# 780-00041_rev1_Front_Panel_Mirror_Cell_C.net
KiCad netlist of a schematic drawn in Altium Designer
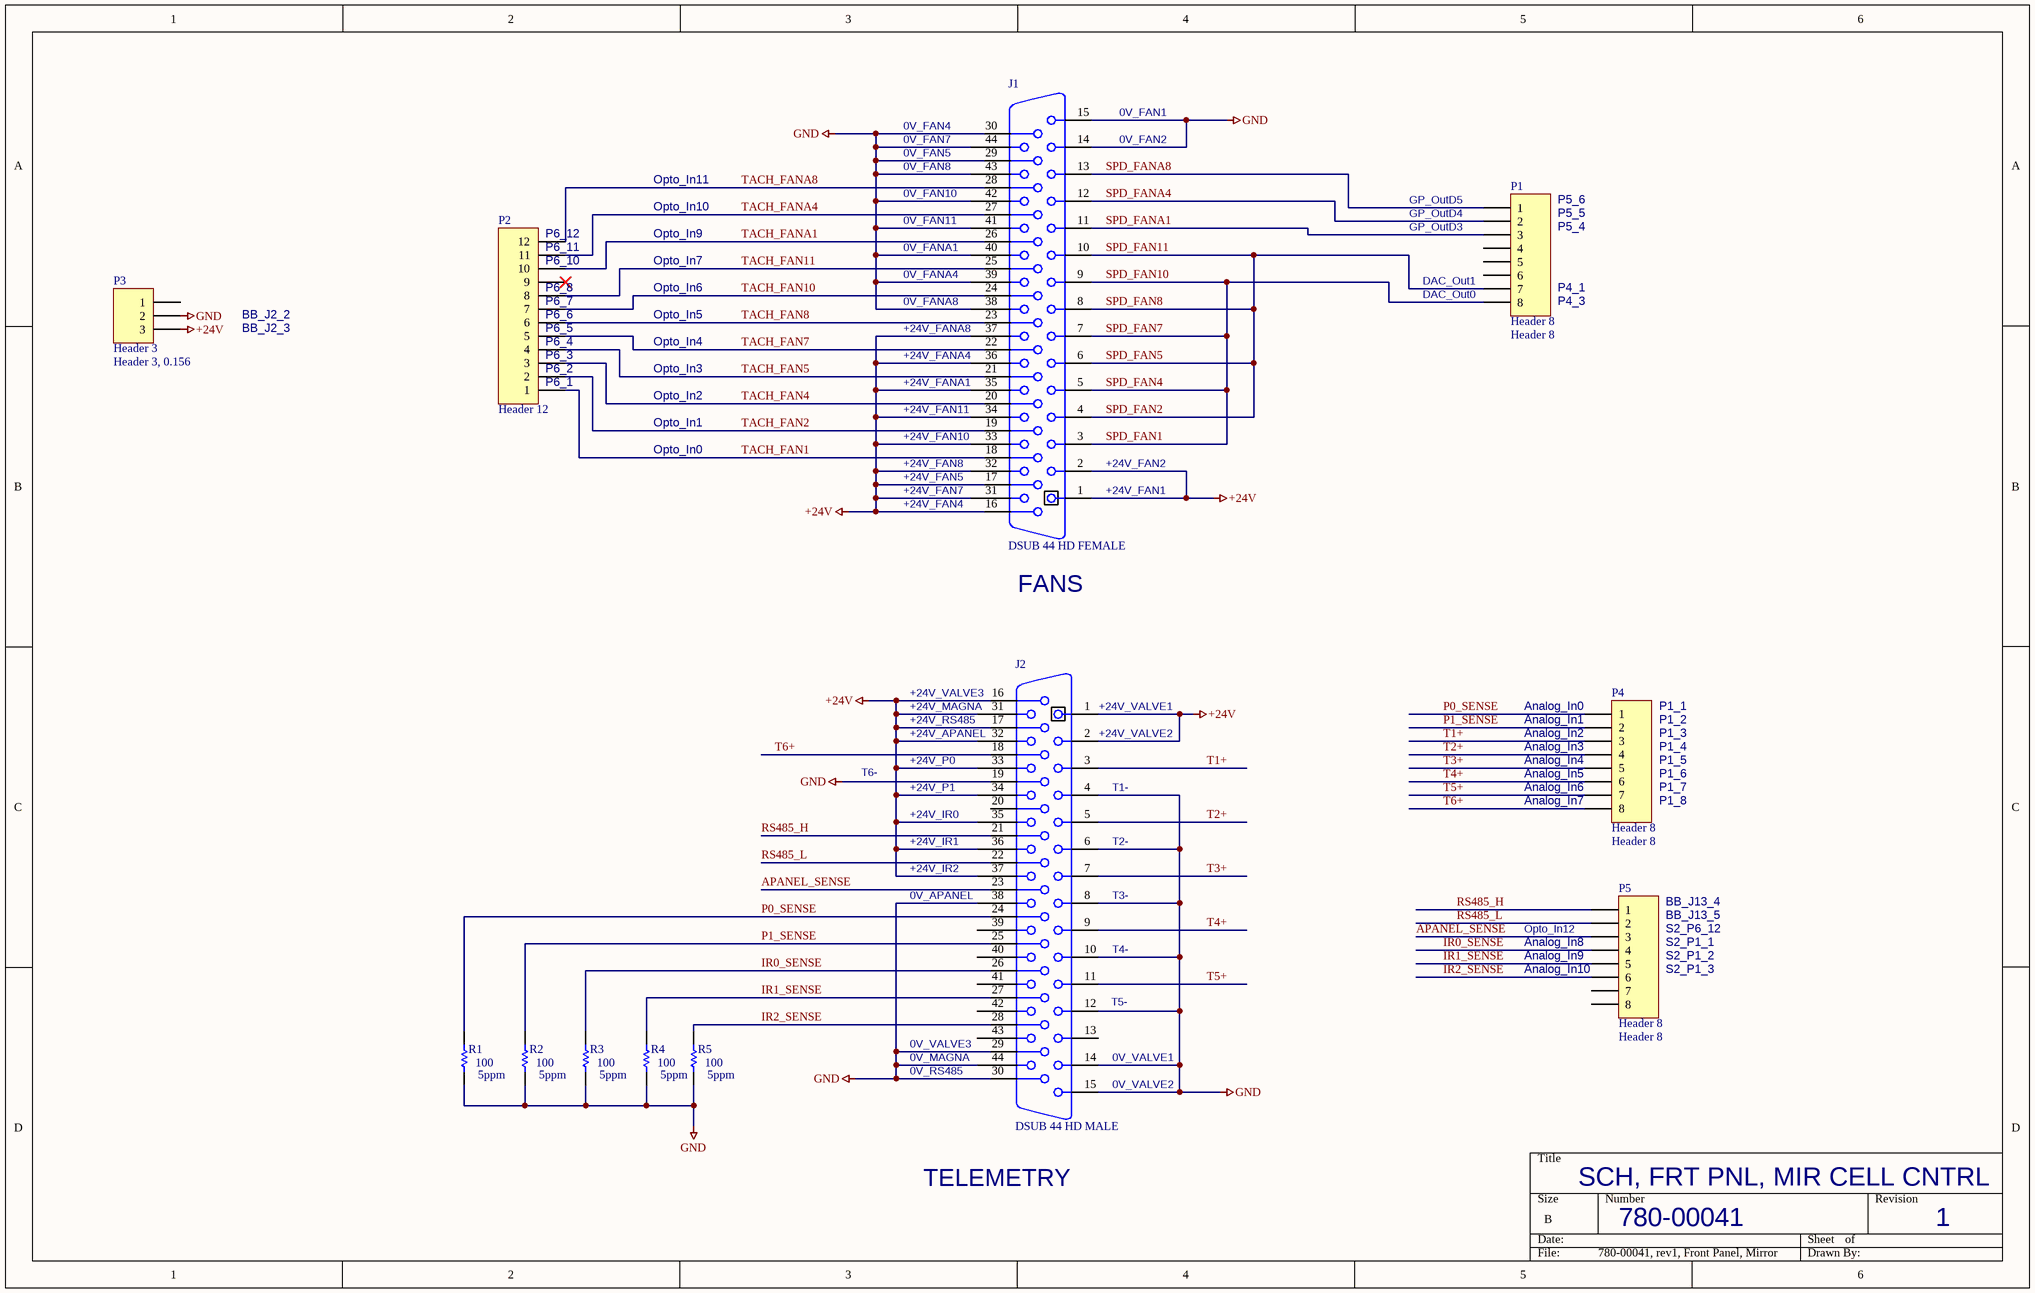
[diagram p0: 780-00041, rev1, Front Panel, Mirror Cell Controller.SchDoc]

(export (version "E")
  (design (tool "Eeschema 10.0.6"))
  (components
    (comp (ref "J1")
      (value "DSUB 44 HD FEMALE")
      (footprint "CONN DB44 HD FEM SOCKETS PCB")
      (description "Receptacle Assembly, 44 PIN")
      (fields (field (name "MANUFACTURER") "fci"))
      (libsource (lib "Richs Schematic Components") (part "DSUB 44 HD FEMALE"))
    )
    (comp (ref "J2")
      (value "DSUB 44 HD MALE")
      (footprint "CONN DB44 HD MALE PINS PCB")
      (description "Receptacle Assembly, 44 PIN")
      (fields (field (name "MANUFACTURER") "FCI"))
      (libsource (lib "Richs Schematic Components") (part "DSUB 44 HD MALE"))
    )
    (comp (ref "P1")
      (value "Header 8")
      (footprint "HDR1X8 for IDC")
      (description "Header, 8-Pin")
      (fields (field (name "MANUFACTURER") "tyco") (field (name "ALTIUM_VALUE") "Header 8"))
      (libsource (lib "Richs Schematic Components") (part "Header 8"))
    )
    (comp (ref "P2")
      (value "Header 12")
      (footprint "HDR1X12 for IDC")
      (description "Header, 12-Pin")
      (fields (field (name "MANUFACTURER") "Tyco"))
      (libsource (lib "Richs Schematic Components") (part "Header 12"))
    )
    (comp (ref "P3")
      (value "Header 3")
      (footprint "HDR 1X3 0.156\"")
      (description "Header, 3-Pin, 0.156")
      (fields (field (name "ALTIUM_VALUE") "Header 3, 0.156"))
      (libsource (lib "Richs Schematic Components") (part "Header 3, 0.156"))
    )
    (comp (ref "P4")
      (value "Header 8")
      (footprint "HDR1X8 for IDC")
      (description "Header, 8-Pin")
      (fields (field (name "MANUFACTURER") "tyco") (field (name "ALTIUM_VALUE") "Header 8"))
      (libsource (lib "Richs Schematic Components") (part "Header 8"))
    )
    (comp (ref "P5")
      (value "Header 8")
      (footprint "HDR1X8 for IDC")
      (description "Header, 8-Pin")
      (fields (field (name "MANUFACTURER") "tyco") (field (name "ALTIUM_VALUE") "Header 8"))
      (libsource (lib "Richs Schematic Components") (part "Header 8"))
    )
    (comp (ref "R1")
      (value "5ppm")
      (footprint "SMD_0805")
      (description "Resistor 0805")
      (fields (field (name "MANUFACTURER") "Vishay/Dale") (field (name "ALTIUM_VALUE") "100"))
      (libsource (lib "Richs Schematic Components") (part "Res SMD"))
    )
    (comp (ref "R2")
      (value "5ppm")
      (footprint "SMD_0805")
      (description "Resistor 0805")
      (fields (field (name "MANUFACTURER") "Vishay/Dale") (field (name "ALTIUM_VALUE") "100"))
      (libsource (lib "Richs Schematic Components") (part "Res SMD"))
    )
    (comp (ref "R3")
      (value "5ppm")
      (footprint "SMD_0805")
      (description "Resistor 0805")
      (fields (field (name "MANUFACTURER") "Vishay/Dale") (field (name "ALTIUM_VALUE") "100"))
      (libsource (lib "Richs Schematic Components") (part "Res SMD"))
    )
    (comp (ref "R4")
      (value "5ppm")
      (footprint "SMD_0805")
      (description "Resistor 0805")
      (fields (field (name "MANUFACTURER") "Vishay/Dale") (field (name "ALTIUM_VALUE") "100"))
      (libsource (lib "Richs Schematic Components") (part "Res SMD"))
    )
    (comp (ref "R5")
      (value "5ppm")
      (footprint "SMD_0805")
      (description "Resistor 0805")
      (fields (field (name "MANUFACTURER") "Vishay/Dale") (field (name "ALTIUM_VALUE") "100"))
      (libsource (lib "Richs Schematic Components") (part "Res SMD"))
    )
  )
  (nets
    (net (code "1") (name "+24V") (class "Default")
      (node (ref "J1") (pin "1") (pintype "passive"))
      (node (ref "J1") (pin "16") (pintype "passive"))
      (node (ref "J1") (pin "17") (pintype "passive"))
      (node (ref "J1") (pin "2") (pintype "passive"))
      (node (ref "J1") (pin "31") (pintype "passive"))
      (node (ref "J1") (pin "32") (pintype "passive"))
      (node (ref "J1") (pin "33") (pintype "passive"))
      (node (ref "J1") (pin "34") (pintype "passive"))
      (node (ref "J1") (pin "35") (pintype "passive"))
      (node (ref "J1") (pin "36") (pintype "passive"))
      (node (ref "J1") (pin "37") (pintype "passive"))
      (node (ref "J2") (pin "1") (pintype "passive"))
      (node (ref "J2") (pin "16") (pintype "passive"))
      (node (ref "J2") (pin "17") (pintype "passive"))
      (node (ref "J2") (pin "2") (pintype "passive"))
      (node (ref "J2") (pin "31") (pintype "passive"))
      (node (ref "J2") (pin "32") (pintype "passive"))
      (node (ref "J2") (pin "33") (pintype "passive"))
      (node (ref "J2") (pin "34") (pintype "passive"))
      (node (ref "J2") (pin "35") (pintype "passive"))
      (node (ref "J2") (pin "36") (pintype "passive"))
      (node (ref "J2") (pin "37") (pintype "passive"))
      (node (ref "P3") (pin "3") (pinfunction "3_3") (pintype "passive"))
    )
    (net (code "2") (name "/APANEL_SENSE") (class "Default")
      (node (ref "J2") (pin "23") (pintype "passive"))
      (node (ref "P5") (pin "3") (pinfunction "3_3") (pintype "passive"))
    )
    (net (code "3") (name "/IR0_SENSE") (class "Default")
      (node (ref "J2") (pin "26") (pintype "passive"))
      (node (ref "P5") (pin "4") (pinfunction "4_4") (pintype "passive"))
      (node (ref "R3") (pin "2") (pinfunction "2_2") (pintype "passive"))
    )
    (net (code "4") (name "/IR1_SENSE") (class "Default")
      (node (ref "J2") (pin "27") (pintype "passive"))
      (node (ref "P5") (pin "5") (pinfunction "5_5") (pintype "passive"))
      (node (ref "R4") (pin "2") (pinfunction "2_2") (pintype "passive"))
    )
    (net (code "5") (name "/IR2_SENSE") (class "Default")
      (node (ref "J2") (pin "28") (pintype "passive"))
      (node (ref "P5") (pin "6") (pinfunction "6_6") (pintype "passive"))
      (node (ref "R5") (pin "2") (pinfunction "2_2") (pintype "passive"))
    )
    (net (code "6") (name "/P0_SENSE") (class "Default")
      (node (ref "J2") (pin "24") (pintype "passive"))
      (node (ref "P4") (pin "1") (pinfunction "1_1") (pintype "passive"))
      (node (ref "R1") (pin "2") (pinfunction "2_2") (pintype "passive"))
    )
    (net (code "7") (name "/P1_SENSE") (class "Default")
      (node (ref "J2") (pin "25") (pintype "passive"))
      (node (ref "P4") (pin "2") (pinfunction "2_2") (pintype "passive"))
      (node (ref "R2") (pin "2") (pinfunction "2_2") (pintype "passive"))
    )
    (net (code "8") (name "/RS485_H") (class "Default")
      (node (ref "J2") (pin "21") (pintype "passive"))
      (node (ref "P5") (pin "1") (pinfunction "1_1") (pintype "passive"))
    )
    (net (code "9") (name "/RS485_L") (class "Default")
      (node (ref "J2") (pin "22") (pintype "passive"))
      (node (ref "P5") (pin "2") (pinfunction "2_2") (pintype "passive"))
    )
    (net (code "10") (name "/SPD_FAN1") (class "Default")
      (node (ref "J1") (pin "3") (pintype "passive"))
      (node (ref "J1") (pin "5") (pintype "passive"))
      (node (ref "J1") (pin "7") (pintype "passive"))
      (node (ref "J1") (pin "9") (pintype "passive"))
      (node (ref "P1") (pin "8") (pinfunction "8_8") (pintype "passive"))
    )
    (net (code "11") (name "/SPD_FAN11") (class "Default")
      (node (ref "J1") (pin "10") (pintype "passive"))
      (node (ref "J1") (pin "4") (pintype "passive"))
      (node (ref "J1") (pin "6") (pintype "passive"))
      (node (ref "J1") (pin "8") (pintype "passive"))
      (node (ref "P1") (pin "7") (pinfunction "7_7") (pintype "passive"))
    )
    (net (code "12") (name "/SPD_FANA1") (class "Default")
      (node (ref "J1") (pin "11") (pintype "passive"))
      (node (ref "P1") (pin "3") (pinfunction "3_3") (pintype "passive"))
    )
    (net (code "13") (name "/SPD_FANA4") (class "Default")
      (node (ref "J1") (pin "12") (pintype "passive"))
      (node (ref "P1") (pin "2") (pinfunction "2_2") (pintype "passive"))
    )
    (net (code "14") (name "/SPD_FANA8") (class "Default")
      (node (ref "J1") (pin "13") (pintype "passive"))
      (node (ref "P1") (pin "1") (pinfunction "1_1") (pintype "passive"))
    )
    (net (code "15") (name "/T1+") (class "Default")
      (node (ref "J2") (pin "3") (pintype "passive"))
      (node (ref "P4") (pin "3") (pinfunction "3_3") (pintype "passive"))
    )
    (net (code "16") (name "/T2+") (class "Default")
      (node (ref "J2") (pin "5") (pintype "passive"))
      (node (ref "P4") (pin "4") (pinfunction "4_4") (pintype "passive"))
    )
    (net (code "17") (name "/T3+") (class "Default")
      (node (ref "J2") (pin "7") (pintype "passive"))
      (node (ref "P4") (pin "5") (pinfunction "5_5") (pintype "passive"))
    )
    (net (code "18") (name "/T4+") (class "Default")
      (node (ref "J2") (pin "9") (pintype "passive"))
      (node (ref "P4") (pin "6") (pinfunction "6_6") (pintype "passive"))
    )
    (net (code "19") (name "/T5+") (class "Default")
      (node (ref "J2") (pin "11") (pintype "passive"))
      (node (ref "P4") (pin "7") (pinfunction "7_7") (pintype "passive"))
    )
    (net (code "20") (name "/T6+") (class "Default")
      (node (ref "J2") (pin "18") (pintype "passive"))
      (node (ref "P4") (pin "8") (pinfunction "8_8") (pintype "passive"))
    )
    (net (code "21") (name "/TACH_FAN1") (class "Default")
      (node (ref "J1") (pin "18") (pintype "passive"))
      (node (ref "P2") (pin "1") (pinfunction "1_1") (pintype "passive"))
    )
    (net (code "22") (name "/TACH_FAN2") (class "Default")
      (node (ref "J1") (pin "19") (pintype "passive"))
      (node (ref "P2") (pin "2") (pinfunction "2_2") (pintype "passive"))
    )
    (net (code "23") (name "/TACH_FAN4") (class "Default")
      (node (ref "J1") (pin "20") (pintype "passive"))
      (node (ref "P2") (pin "3") (pinfunction "3_3") (pintype "passive"))
    )
    (net (code "24") (name "/TACH_FAN5") (class "Default")
      (node (ref "J1") (pin "21") (pintype "passive"))
      (node (ref "P2") (pin "4") (pinfunction "4_4") (pintype "passive"))
    )
    (net (code "25") (name "/TACH_FAN7") (class "Default")
      (node (ref "J1") (pin "22") (pintype "passive"))
      (node (ref "P2") (pin "5") (pinfunction "5_5") (pintype "passive"))
    )
    (net (code "26") (name "/TACH_FAN8") (class "Default")
      (node (ref "J1") (pin "23") (pintype "passive"))
      (node (ref "P2") (pin "6") (pinfunction "6_6") (pintype "passive"))
    )
    (net (code "27") (name "/TACH_FAN10") (class "Default")
      (node (ref "J1") (pin "24") (pintype "passive"))
      (node (ref "P2") (pin "7") (pinfunction "7_7") (pintype "passive"))
    )
    (net (code "28") (name "/TACH_FAN11") (class "Default")
      (node (ref "J1") (pin "25") (pintype "passive"))
      (node (ref "P2") (pin "8") (pinfunction "8_8") (pintype "passive"))
    )
    (net (code "29") (name "/TACH_FANA1") (class "Default")
      (node (ref "J1") (pin "26") (pintype "passive"))
      (node (ref "P2") (pin "10") (pinfunction "10_10") (pintype "passive"))
    )
    (net (code "30") (name "/TACH_FANA4") (class "Default")
      (node (ref "J1") (pin "27") (pintype "passive"))
      (node (ref "P2") (pin "11") (pinfunction "11_11") (pintype "passive"))
    )
    (net (code "31") (name "/TACH_FANA8") (class "Default")
      (node (ref "J1") (pin "28") (pintype "passive"))
      (node (ref "P2") (pin "12") (pinfunction "12_12") (pintype "passive"))
    )
    (net (code "32") (name "GND") (class "Default")
      (node (ref "J1") (pin "14") (pintype "passive"))
      (node (ref "J1") (pin "15") (pintype "passive"))
      (node (ref "J1") (pin "29") (pintype "passive"))
      (node (ref "J1") (pin "30") (pintype "passive"))
      (node (ref "J1") (pin "38") (pintype "passive"))
      (node (ref "J1") (pin "39") (pintype "passive"))
      (node (ref "J1") (pin "40") (pintype "passive"))
      (node (ref "J1") (pin "41") (pintype "passive"))
      (node (ref "J1") (pin "42") (pintype "passive"))
      (node (ref "J1") (pin "43") (pintype "passive"))
      (node (ref "J1") (pin "44") (pintype "passive"))
      (node (ref "J2") (pin "10") (pintype "passive"))
      (node (ref "J2") (pin "12") (pintype "passive"))
      (node (ref "J2") (pin "14") (pintype "passive"))
      (node (ref "J2") (pin "15") (pintype "passive"))
      (node (ref "J2") (pin "19") (pintype "passive"))
      (node (ref "J2") (pin "29") (pintype "passive"))
      (node (ref "J2") (pin "30") (pintype "passive"))
      (node (ref "J2") (pin "38") (pintype "passive"))
      (node (ref "J2") (pin "4") (pintype "passive"))
      (node (ref "J2") (pin "44") (pintype "passive"))
      (node (ref "J2") (pin "6") (pintype "passive"))
      (node (ref "J2") (pin "8") (pintype "passive"))
      (node (ref "P3") (pin "2") (pinfunction "2_2") (pintype "passive"))
      (node (ref "R1") (pin "1") (pinfunction "1_1") (pintype "passive"))
      (node (ref "R2") (pin "1") (pinfunction "1_1") (pintype "passive"))
      (node (ref "R3") (pin "1") (pinfunction "1_1") (pintype "passive"))
      (node (ref "R4") (pin "1") (pinfunction "1_1") (pintype "passive"))
      (node (ref "R5") (pin "1") (pinfunction "1_1") (pintype "passive"))
    )
    (net (code "33") (name "unconnected-(J2-Pad13)") (class "Default")
      (node (ref "J2") (pin "13") (pintype "passive"))
    )
    (net (code "34") (name "unconnected-(J2-Pad20)") (class "Default")
      (node (ref "J2") (pin "20") (pintype "passive"))
    )
    (net (code "35") (name "unconnected-(J2-Pad39)") (class "Default")
      (node (ref "J2") (pin "39") (pintype "passive"))
    )
    (net (code "36") (name "unconnected-(J2-Pad40)") (class "Default")
      (node (ref "J2") (pin "40") (pintype "passive"))
    )
    (net (code "37") (name "unconnected-(J2-Pad41)") (class "Default")
      (node (ref "J2") (pin "41") (pintype "passive"))
    )
    (net (code "38") (name "unconnected-(J2-Pad42)") (class "Default")
      (node (ref "J2") (pin "42") (pintype "passive"))
    )
    (net (code "39") (name "unconnected-(J2-Pad43)") (class "Default")
      (node (ref "J2") (pin "43") (pintype "passive"))
    )
    (net (code "40") (name "unconnected-(P1-Pad4)") (class "Default")
      (node (ref "P1") (pin "4") (pinfunction "4_4") (pintype "passive"))
    )
    (net (code "41") (name "unconnected-(P1-Pad5)") (class "Default")
      (node (ref "P1") (pin "5") (pinfunction "5_5") (pintype "passive"))
    )
    (net (code "42") (name "unconnected-(P1-Pad6)") (class "Default")
      (node (ref "P1") (pin "6") (pinfunction "6_6") (pintype "passive"))
    )
    (net (code "43") (name "unconnected-(P2-Pad9)") (class "Default")
      (node (ref "P2") (pin "9") (pinfunction "9_9") (pintype "passive+no_connect"))
    )
    (net (code "44") (name "unconnected-(P3-Pad1)") (class "Default")
      (node (ref "P3") (pin "1") (pinfunction "1_1") (pintype "passive"))
    )
    (net (code "45") (name "unconnected-(P5-Pad7)") (class "Default")
      (node (ref "P5") (pin "7") (pinfunction "7_7") (pintype "passive"))
    )
    (net (code "46") (name "unconnected-(P5-Pad8)") (class "Default")
      (node (ref "P5") (pin "8") (pinfunction "8_8") (pintype "passive"))
    )
  )
)
